# RT1052_MB.net
KiCad netlist of a schematic drawn in Altium Designer
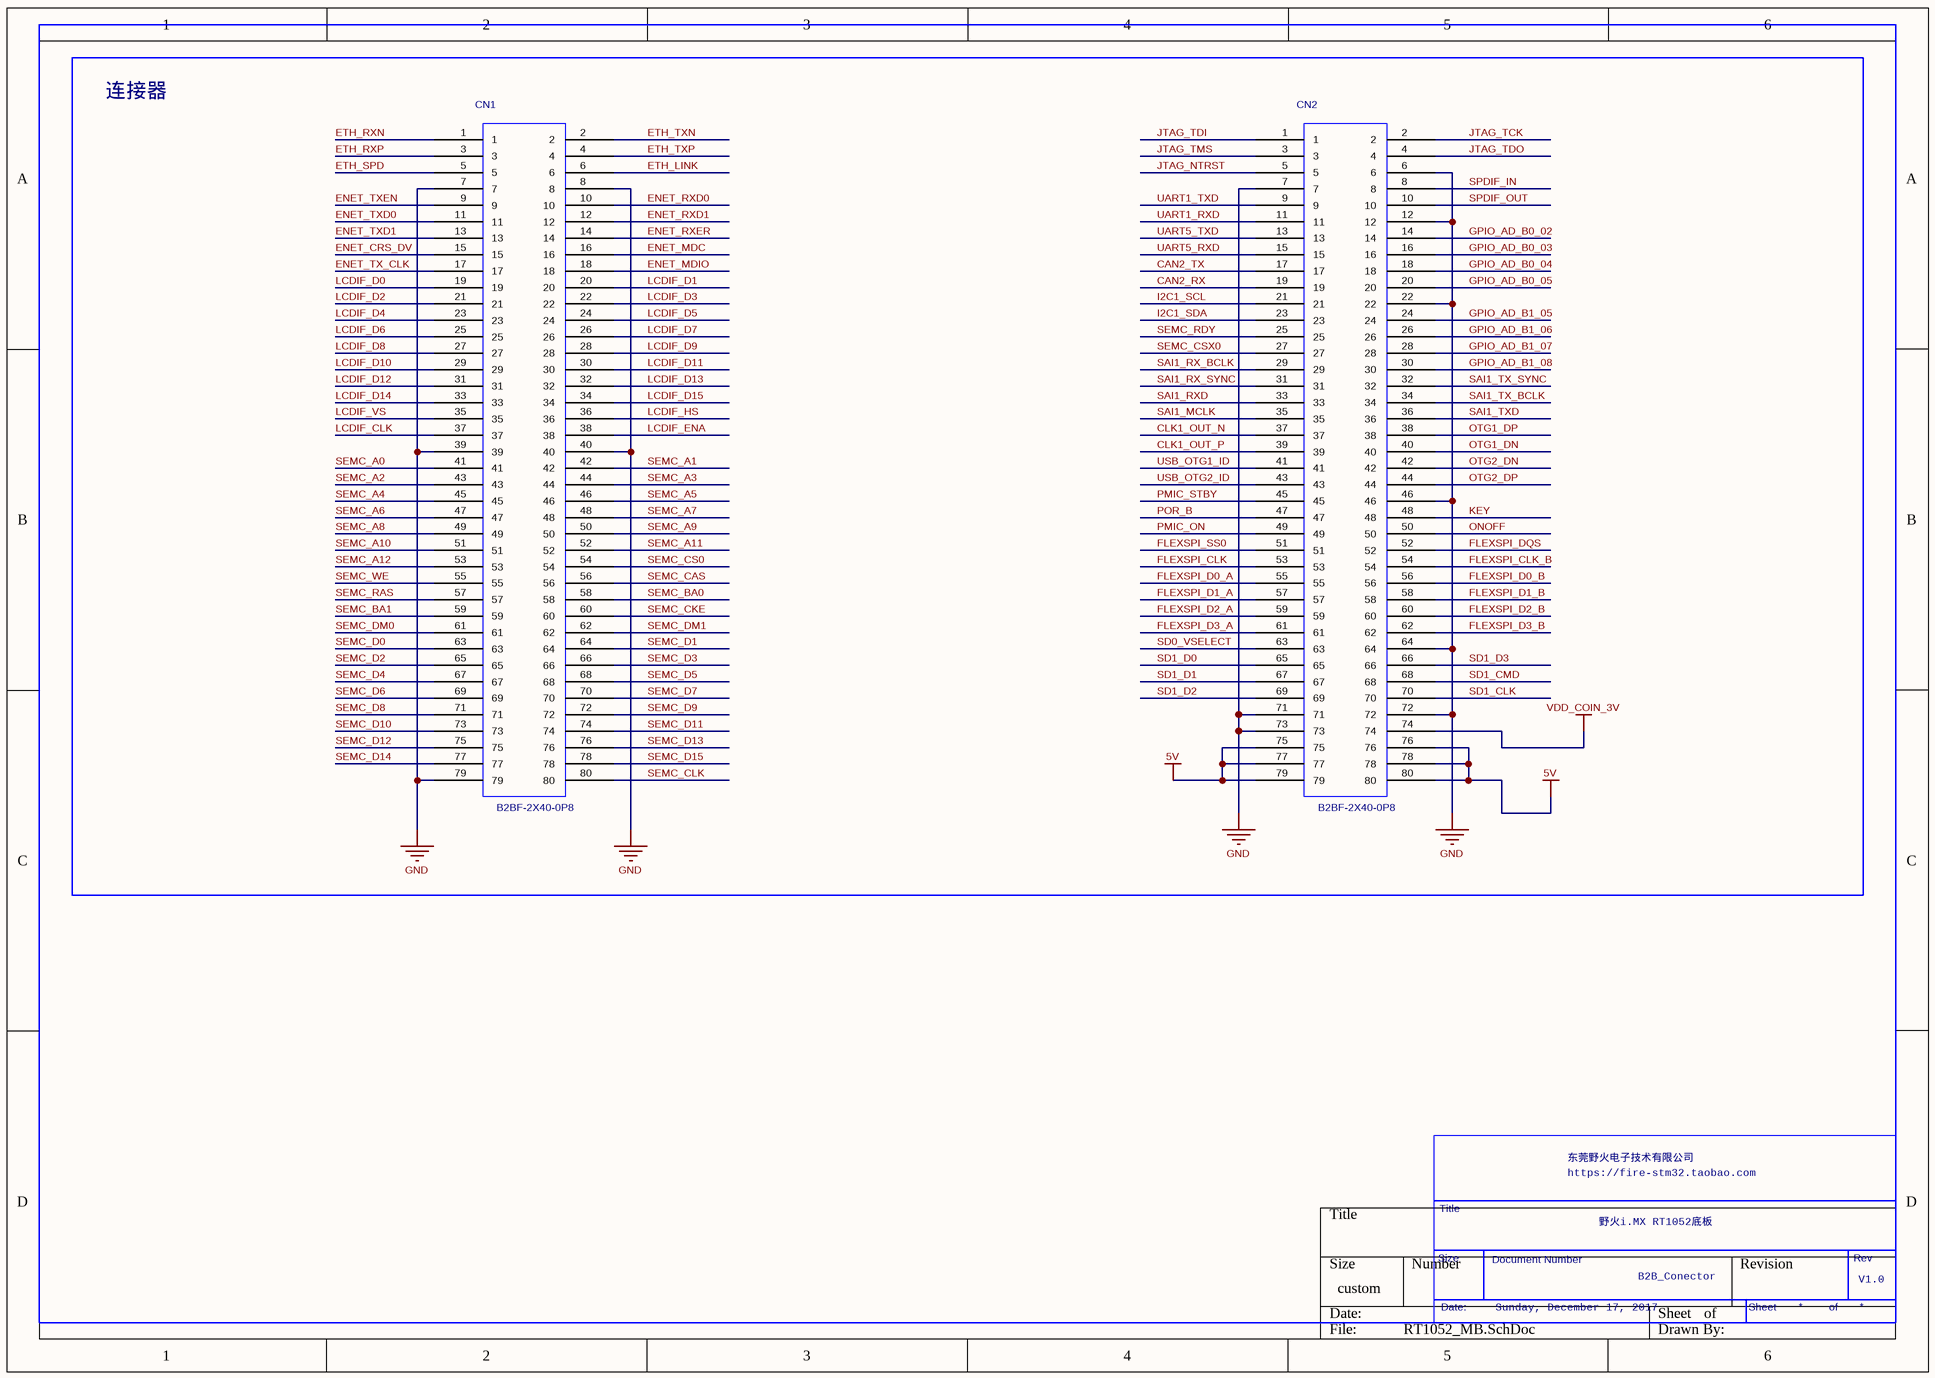
[diagram p0: RT1052_MB.SchDoc]

(export (version "E")
  (design (tool "Eeschema 10.0.6"))
  (components
    (comp (ref "CN1")
      (value "B2BF-2X40-0P8")
      (footprint "B2BF-2X40-0P8")
      (fields (field (name "Comment") "B2B_2X40_0_8MM"))
      (libsource (lib "*") (part "B2B_2X40_0_8MM"))
    )
    (comp (ref "CN2")
      (value "B2BF-2X40-0P8")
      (footprint "B2BF-2X40-0P8")
      (fields (field (name "Comment") "B2B_2X40_0_8MM"))
      (libsource (lib "*") (part "B2B_2X40_0_8MM"))
    )
  )
  (nets
    (net (code "1") (name "/CAN2_RX") (class "Default")
      (node (ref "CN2") (pin "19") (pinfunction "19_19") (pintype "passive"))
    )
    (net (code "2") (name "/CAN2_TX") (class "Default")
      (node (ref "CN2") (pin "17") (pinfunction "17_17") (pintype "passive"))
    )
    (net (code "3") (name "/CLK1_OUT_N") (class "Default")
      (node (ref "CN2") (pin "37") (pinfunction "37_37") (pintype "passive"))
    )
    (net (code "4") (name "/CLK1_OUT_P") (class "Default")
      (node (ref "CN2") (pin "39") (pinfunction "39_39") (pintype "passive"))
    )
    (net (code "5") (name "/ENET_CRS_DV") (class "Default")
      (node (ref "CN1") (pin "15") (pinfunction "15_15") (pintype "passive"))
    )
    (net (code "6") (name "/ENET_MDC") (class "Default")
      (node (ref "CN1") (pin "16") (pinfunction "16_16") (pintype "passive"))
    )
    (net (code "7") (name "/ENET_MDIO") (class "Default")
      (node (ref "CN1") (pin "18") (pinfunction "18_18") (pintype "passive"))
    )
    (net (code "8") (name "/ENET_RXD0") (class "Default")
      (node (ref "CN1") (pin "10") (pinfunction "10_10") (pintype "passive"))
    )
    (net (code "9") (name "/ENET_RXD1") (class "Default")
      (node (ref "CN1") (pin "12") (pinfunction "12_12") (pintype "passive"))
    )
    (net (code "10") (name "/ENET_RXER") (class "Default")
      (node (ref "CN1") (pin "14") (pinfunction "14_14") (pintype "passive"))
    )
    (net (code "11") (name "/ENET_TXD0") (class "Default")
      (node (ref "CN1") (pin "11") (pinfunction "11_11") (pintype "passive"))
    )
    (net (code "12") (name "/ENET_TXD1") (class "Default")
      (node (ref "CN1") (pin "13") (pinfunction "13_13") (pintype "passive"))
    )
    (net (code "13") (name "/ENET_TXEN") (class "Default")
      (node (ref "CN1") (pin "9") (pinfunction "9_9") (pintype "passive"))
    )
    (net (code "14") (name "/ENET_TX_CLK") (class "Default")
      (node (ref "CN1") (pin "17") (pinfunction "17_17") (pintype "passive"))
    )
    (net (code "15") (name "/ETH_LINK") (class "Default")
      (node (ref "CN1") (pin "6") (pinfunction "6_6") (pintype "passive"))
    )
    (net (code "16") (name "/ETH_RXN") (class "Default")
      (node (ref "CN1") (pin "1") (pinfunction "1_1") (pintype "passive"))
    )
    (net (code "17") (name "/ETH_RXP") (class "Default")
      (node (ref "CN1") (pin "3") (pinfunction "3_3") (pintype "passive"))
    )
    (net (code "18") (name "/ETH_SPD") (class "Default")
      (node (ref "CN1") (pin "5") (pinfunction "5_5") (pintype "passive"))
    )
    (net (code "19") (name "/ETH_TXN") (class "Default")
      (node (ref "CN1") (pin "2") (pinfunction "2_2") (pintype "passive"))
    )
    (net (code "20") (name "/ETH_TXP") (class "Default")
      (node (ref "CN1") (pin "4") (pinfunction "4_4") (pintype "passive"))
    )
    (net (code "21") (name "/FLEXSPI_CLK") (class "Default")
      (node (ref "CN2") (pin "53") (pinfunction "53_53") (pintype "passive"))
    )
    (net (code "22") (name "/FLEXSPI_CLK_B") (class "Default")
      (node (ref "CN2") (pin "54") (pinfunction "54_54") (pintype "passive"))
    )
    (net (code "23") (name "/FLEXSPI_D0_A") (class "Default")
      (node (ref "CN2") (pin "55") (pinfunction "55_55") (pintype "passive"))
    )
    (net (code "24") (name "/FLEXSPI_D0_B") (class "Default")
      (node (ref "CN2") (pin "56") (pinfunction "56_56") (pintype "passive"))
    )
    (net (code "25") (name "/FLEXSPI_D1_A") (class "Default")
      (node (ref "CN2") (pin "57") (pinfunction "57_57") (pintype "passive"))
    )
    (net (code "26") (name "/FLEXSPI_D1_B") (class "Default")
      (node (ref "CN2") (pin "58") (pinfunction "58_58") (pintype "passive"))
    )
    (net (code "27") (name "/FLEXSPI_D2_A") (class "Default")
      (node (ref "CN2") (pin "59") (pinfunction "59_59") (pintype "passive"))
    )
    (net (code "28") (name "/FLEXSPI_D2_B") (class "Default")
      (node (ref "CN2") (pin "60") (pinfunction "60_60") (pintype "passive"))
    )
    (net (code "29") (name "/FLEXSPI_D3_A") (class "Default")
      (node (ref "CN2") (pin "61") (pinfunction "61_61") (pintype "passive"))
    )
    (net (code "30") (name "/FLEXSPI_D3_B") (class "Default")
      (node (ref "CN2") (pin "62") (pinfunction "62_62") (pintype "passive"))
    )
    (net (code "31") (name "/FLEXSPI_DQS") (class "Default")
      (node (ref "CN2") (pin "52") (pinfunction "52_52") (pintype "passive"))
    )
    (net (code "32") (name "/FLEXSPI_SS0") (class "Default")
      (node (ref "CN2") (pin "51") (pinfunction "51_51") (pintype "passive"))
    )
    (net (code "33") (name "/GPIO_AD_B0_02") (class "Default")
      (node (ref "CN2") (pin "14") (pinfunction "14_14") (pintype "passive"))
    )
    (net (code "34") (name "/GPIO_AD_B0_03") (class "Default")
      (node (ref "CN2") (pin "16") (pinfunction "16_16") (pintype "passive"))
    )
    (net (code "35") (name "/GPIO_AD_B0_04") (class "Default")
      (node (ref "CN2") (pin "18") (pinfunction "18_18") (pintype "passive"))
    )
    (net (code "36") (name "/GPIO_AD_B0_05") (class "Default")
      (node (ref "CN2") (pin "20") (pinfunction "20_20") (pintype "passive"))
    )
    (net (code "37") (name "/GPIO_AD_B1_05") (class "Default")
      (node (ref "CN2") (pin "24") (pinfunction "24_24") (pintype "passive"))
    )
    (net (code "38") (name "/GPIO_AD_B1_06") (class "Default")
      (node (ref "CN2") (pin "26") (pinfunction "26_26") (pintype "passive"))
    )
    (net (code "39") (name "/GPIO_AD_B1_07") (class "Default")
      (node (ref "CN2") (pin "28") (pinfunction "28_28") (pintype "passive"))
    )
    (net (code "40") (name "/GPIO_AD_B1_08") (class "Default")
      (node (ref "CN2") (pin "30") (pinfunction "30_30") (pintype "passive"))
    )
    (net (code "41") (name "/I2C1_SCL") (class "Default")
      (node (ref "CN2") (pin "21") (pinfunction "21_21") (pintype "passive"))
    )
    (net (code "42") (name "/I2C1_SDA") (class "Default")
      (node (ref "CN2") (pin "23") (pinfunction "23_23") (pintype "passive"))
    )
    (net (code "43") (name "/JTAG_NTRST") (class "Default")
      (node (ref "CN2") (pin "5") (pinfunction "5_5") (pintype "passive"))
    )
    (net (code "44") (name "/JTAG_TCK") (class "Default")
      (node (ref "CN2") (pin "2") (pinfunction "2_2") (pintype "passive"))
    )
    (net (code "45") (name "/JTAG_TDI") (class "Default")
      (node (ref "CN2") (pin "1") (pinfunction "1_1") (pintype "passive"))
    )
    (net (code "46") (name "/JTAG_TDO") (class "Default")
      (node (ref "CN2") (pin "4") (pinfunction "4_4") (pintype "passive"))
    )
    (net (code "47") (name "/JTAG_TMS") (class "Default")
      (node (ref "CN2") (pin "3") (pinfunction "3_3") (pintype "passive"))
    )
    (net (code "48") (name "/KEY") (class "Default")
      (node (ref "CN2") (pin "48") (pinfunction "48_48") (pintype "passive"))
    )
    (net (code "49") (name "/LCDIF_CLK") (class "Default")
      (node (ref "CN1") (pin "37") (pinfunction "37_37") (pintype "passive"))
    )
    (net (code "50") (name "/LCDIF_D0") (class "Default")
      (node (ref "CN1") (pin "19") (pinfunction "19_19") (pintype "passive"))
    )
    (net (code "51") (name "/LCDIF_D1") (class "Default")
      (node (ref "CN1") (pin "20") (pinfunction "20_20") (pintype "passive"))
    )
    (net (code "52") (name "/LCDIF_D2") (class "Default")
      (node (ref "CN1") (pin "21") (pinfunction "21_21") (pintype "passive"))
    )
    (net (code "53") (name "/LCDIF_D3") (class "Default")
      (node (ref "CN1") (pin "22") (pinfunction "22_22") (pintype "passive"))
    )
    (net (code "54") (name "/LCDIF_D4") (class "Default")
      (node (ref "CN1") (pin "23") (pinfunction "23_23") (pintype "passive"))
    )
    (net (code "55") (name "/LCDIF_D5") (class "Default")
      (node (ref "CN1") (pin "24") (pinfunction "24_24") (pintype "passive"))
    )
    (net (code "56") (name "/LCDIF_D6") (class "Default")
      (node (ref "CN1") (pin "25") (pinfunction "25_25") (pintype "passive"))
    )
    (net (code "57") (name "/LCDIF_D7") (class "Default")
      (node (ref "CN1") (pin "26") (pinfunction "26_26") (pintype "passive"))
    )
    (net (code "58") (name "/LCDIF_D8") (class "Default")
      (node (ref "CN1") (pin "27") (pinfunction "27_27") (pintype "passive"))
    )
    (net (code "59") (name "/LCDIF_D9") (class "Default")
      (node (ref "CN1") (pin "28") (pinfunction "28_28") (pintype "passive"))
    )
    (net (code "60") (name "/LCDIF_D10") (class "Default")
      (node (ref "CN1") (pin "29") (pinfunction "29_29") (pintype "passive"))
    )
    (net (code "61") (name "/LCDIF_D11") (class "Default")
      (node (ref "CN1") (pin "30") (pinfunction "30_30") (pintype "passive"))
    )
    (net (code "62") (name "/LCDIF_D12") (class "Default")
      (node (ref "CN1") (pin "31") (pinfunction "31_31") (pintype "passive"))
    )
    (net (code "63") (name "/LCDIF_D13") (class "Default")
      (node (ref "CN1") (pin "32") (pinfunction "32_32") (pintype "passive"))
    )
    (net (code "64") (name "/LCDIF_D14") (class "Default")
      (node (ref "CN1") (pin "33") (pinfunction "33_33") (pintype "passive"))
    )
    (net (code "65") (name "/LCDIF_D15") (class "Default")
      (node (ref "CN1") (pin "34") (pinfunction "34_34") (pintype "passive"))
    )
    (net (code "66") (name "/LCDIF_ENA") (class "Default")
      (node (ref "CN1") (pin "38") (pinfunction "38_38") (pintype "passive"))
    )
    (net (code "67") (name "/LCDIF_HS") (class "Default")
      (node (ref "CN1") (pin "36") (pinfunction "36_36") (pintype "passive"))
    )
    (net (code "68") (name "/LCDIF_VS") (class "Default")
      (node (ref "CN1") (pin "35") (pinfunction "35_35") (pintype "passive"))
    )
    (net (code "69") (name "/ONOFF") (class "Default")
      (node (ref "CN2") (pin "50") (pinfunction "50_50") (pintype "passive"))
    )
    (net (code "70") (name "/OTG1_DN") (class "Default")
      (node (ref "CN2") (pin "40") (pinfunction "40_40") (pintype "passive"))
    )
    (net (code "71") (name "/OTG1_DP") (class "Default")
      (node (ref "CN2") (pin "38") (pinfunction "38_38") (pintype "passive"))
    )
    (net (code "72") (name "/OTG2_DN") (class "Default")
      (node (ref "CN2") (pin "42") (pinfunction "42_42") (pintype "passive"))
    )
    (net (code "73") (name "/OTG2_DP") (class "Default")
      (node (ref "CN2") (pin "44") (pinfunction "44_44") (pintype "passive"))
    )
    (net (code "74") (name "/PMIC_ON") (class "Default")
      (node (ref "CN2") (pin "49") (pinfunction "49_49") (pintype "passive"))
    )
    (net (code "75") (name "/PMIC_STBY") (class "Default")
      (node (ref "CN2") (pin "45") (pinfunction "45_45") (pintype "passive"))
    )
    (net (code "76") (name "/POR_B") (class "Default")
      (node (ref "CN2") (pin "47") (pinfunction "47_47") (pintype "passive"))
    )
    (net (code "77") (name "/SAI1_MCLK") (class "Default")
      (node (ref "CN2") (pin "35") (pinfunction "35_35") (pintype "passive"))
    )
    (net (code "78") (name "/SAI1_RXD") (class "Default")
      (node (ref "CN2") (pin "33") (pinfunction "33_33") (pintype "passive"))
    )
    (net (code "79") (name "/SAI1_RX_BCLK") (class "Default")
      (node (ref "CN2") (pin "29") (pinfunction "29_29") (pintype "passive"))
    )
    (net (code "80") (name "/SAI1_RX_SYNC") (class "Default")
      (node (ref "CN2") (pin "31") (pinfunction "31_31") (pintype "passive"))
    )
    (net (code "81") (name "/SAI1_TXD") (class "Default")
      (node (ref "CN2") (pin "36") (pinfunction "36_36") (pintype "passive"))
    )
    (net (code "82") (name "/SAI1_TX_BCLK") (class "Default")
      (node (ref "CN2") (pin "34") (pinfunction "34_34") (pintype "passive"))
    )
    (net (code "83") (name "/SAI1_TX_SYNC") (class "Default")
      (node (ref "CN2") (pin "32") (pinfunction "32_32") (pintype "passive"))
    )
    (net (code "84") (name "/SD0_VSELECT") (class "Default")
      (node (ref "CN2") (pin "63") (pinfunction "63_63") (pintype "passive"))
    )
    (net (code "85") (name "/SD1_CLK") (class "Default")
      (node (ref "CN2") (pin "70") (pinfunction "70_70") (pintype "passive"))
    )
    (net (code "86") (name "/SD1_CMD") (class "Default")
      (node (ref "CN2") (pin "68") (pinfunction "68_68") (pintype "passive"))
    )
    (net (code "87") (name "/SD1_D0") (class "Default")
      (node (ref "CN2") (pin "65") (pinfunction "65_65") (pintype "passive"))
    )
    (net (code "88") (name "/SD1_D1") (class "Default")
      (node (ref "CN2") (pin "67") (pinfunction "67_67") (pintype "passive"))
    )
    (net (code "89") (name "/SD1_D2") (class "Default")
      (node (ref "CN2") (pin "69") (pinfunction "69_69") (pintype "passive"))
    )
    (net (code "90") (name "/SD1_D3") (class "Default")
      (node (ref "CN2") (pin "66") (pinfunction "66_66") (pintype "passive"))
    )
    (net (code "91") (name "/SEMC_A0") (class "Default")
      (node (ref "CN1") (pin "41") (pinfunction "41_41") (pintype "passive"))
    )
    (net (code "92") (name "/SEMC_A1") (class "Default")
      (node (ref "CN1") (pin "42") (pinfunction "42_42") (pintype "passive"))
    )
    (net (code "93") (name "/SEMC_A2") (class "Default")
      (node (ref "CN1") (pin "43") (pinfunction "43_43") (pintype "passive"))
    )
    (net (code "94") (name "/SEMC_A3") (class "Default")
      (node (ref "CN1") (pin "44") (pinfunction "44_44") (pintype "passive"))
    )
    (net (code "95") (name "/SEMC_A4") (class "Default")
      (node (ref "CN1") (pin "45") (pinfunction "45_45") (pintype "passive"))
    )
    (net (code "96") (name "/SEMC_A5") (class "Default")
      (node (ref "CN1") (pin "46") (pinfunction "46_46") (pintype "passive"))
    )
    (net (code "97") (name "/SEMC_A6") (class "Default")
      (node (ref "CN1") (pin "47") (pinfunction "47_47") (pintype "passive"))
    )
    (net (code "98") (name "/SEMC_A7") (class "Default")
      (node (ref "CN1") (pin "48") (pinfunction "48_48") (pintype "passive"))
    )
    (net (code "99") (name "/SEMC_A8") (class "Default")
      (node (ref "CN1") (pin "49") (pinfunction "49_49") (pintype "passive"))
    )
    (net (code "100") (name "/SEMC_A9") (class "Default")
      (node (ref "CN1") (pin "50") (pinfunction "50_50") (pintype "passive"))
    )
    (net (code "101") (name "/SEMC_A10") (class "Default")
      (node (ref "CN1") (pin "51") (pinfunction "51_51") (pintype "passive"))
    )
    (net (code "102") (name "/SEMC_A11") (class "Default")
      (node (ref "CN1") (pin "52") (pinfunction "52_52") (pintype "passive"))
    )
    (net (code "103") (name "/SEMC_A12") (class "Default")
      (node (ref "CN1") (pin "53") (pinfunction "53_53") (pintype "passive"))
    )
    (net (code "104") (name "/SEMC_BA0") (class "Default")
      (node (ref "CN1") (pin "58") (pinfunction "58_58") (pintype "passive"))
    )
    (net (code "105") (name "/SEMC_BA1") (class "Default")
      (node (ref "CN1") (pin "59") (pinfunction "59_59") (pintype "passive"))
    )
    (net (code "106") (name "/SEMC_CAS") (class "Default")
      (node (ref "CN1") (pin "56") (pinfunction "56_56") (pintype "passive"))
    )
    (net (code "107") (name "/SEMC_CKE") (class "Default")
      (node (ref "CN1") (pin "60") (pinfunction "60_60") (pintype "passive"))
    )
    (net (code "108") (name "/SEMC_CLK") (class "Default")
      (node (ref "CN1") (pin "80") (pinfunction "80_80") (pintype "passive"))
    )
    (net (code "109") (name "/SEMC_CS0") (class "Default")
      (node (ref "CN1") (pin "54") (pinfunction "54_54") (pintype "passive"))
    )
    (net (code "110") (name "/SEMC_CSX0") (class "Default")
      (node (ref "CN2") (pin "27") (pinfunction "27_27") (pintype "passive"))
    )
    (net (code "111") (name "/SEMC_D0") (class "Default")
      (node (ref "CN1") (pin "63") (pinfunction "63_63") (pintype "passive"))
    )
    (net (code "112") (name "/SEMC_D1") (class "Default")
      (node (ref "CN1") (pin "64") (pinfunction "64_64") (pintype "passive"))
    )
    (net (code "113") (name "/SEMC_D2") (class "Default")
      (node (ref "CN1") (pin "65") (pinfunction "65_65") (pintype "passive"))
    )
    (net (code "114") (name "/SEMC_D3") (class "Default")
      (node (ref "CN1") (pin "66") (pinfunction "66_66") (pintype "passive"))
    )
    (net (code "115") (name "/SEMC_D4") (class "Default")
      (node (ref "CN1") (pin "67") (pinfunction "67_67") (pintype "passive"))
    )
    (net (code "116") (name "/SEMC_D5") (class "Default")
      (node (ref "CN1") (pin "68") (pinfunction "68_68") (pintype "passive"))
    )
    (net (code "117") (name "/SEMC_D6") (class "Default")
      (node (ref "CN1") (pin "69") (pinfunction "69_69") (pintype "passive"))
    )
    (net (code "118") (name "/SEMC_D7") (class "Default")
      (node (ref "CN1") (pin "70") (pinfunction "70_70") (pintype "passive"))
    )
    (net (code "119") (name "/SEMC_D8") (class "Default")
      (node (ref "CN1") (pin "71") (pinfunction "71_71") (pintype "passive"))
    )
    (net (code "120") (name "/SEMC_D9") (class "Default")
      (node (ref "CN1") (pin "72") (pinfunction "72_72") (pintype "passive"))
    )
    (net (code "121") (name "/SEMC_D10") (class "Default")
      (node (ref "CN1") (pin "73") (pinfunction "73_73") (pintype "passive"))
    )
    (net (code "122") (name "/SEMC_D11") (class "Default")
      (node (ref "CN1") (pin "74") (pinfunction "74_74") (pintype "passive"))
    )
    (net (code "123") (name "/SEMC_D12") (class "Default")
      (node (ref "CN1") (pin "75") (pinfunction "75_75") (pintype "passive"))
    )
    (net (code "124") (name "/SEMC_D13") (class "Default")
      (node (ref "CN1") (pin "76") (pinfunction "76_76") (pintype "passive"))
    )
    (net (code "125") (name "/SEMC_D14") (class "Default")
      (node (ref "CN1") (pin "77") (pinfunction "77_77") (pintype "passive"))
    )
    (net (code "126") (name "/SEMC_D15") (class "Default")
      (node (ref "CN1") (pin "78") (pinfunction "78_78") (pintype "passive"))
    )
    (net (code "127") (name "/SEMC_DM0") (class "Default")
      (node (ref "CN1") (pin "61") (pinfunction "61_61") (pintype "passive"))
    )
    (net (code "128") (name "/SEMC_DM1") (class "Default")
      (node (ref "CN1") (pin "62") (pinfunction "62_62") (pintype "passive"))
    )
    (net (code "129") (name "/SEMC_RAS") (class "Default")
      (node (ref "CN1") (pin "57") (pinfunction "57_57") (pintype "passive"))
    )
    (net (code "130") (name "/SEMC_RDY") (class "Default")
      (node (ref "CN2") (pin "25") (pinfunction "25_25") (pintype "passive"))
    )
    (net (code "131") (name "/SEMC_WE") (class "Default")
      (node (ref "CN1") (pin "55") (pinfunction "55_55") (pintype "passive"))
    )
    (net (code "132") (name "/SPDIF_IN") (class "Default")
      (node (ref "CN2") (pin "8") (pinfunction "8_8") (pintype "passive"))
    )
    (net (code "133") (name "/SPDIF_OUT") (class "Default")
      (node (ref "CN2") (pin "10") (pinfunction "10_10") (pintype "passive"))
    )
    (net (code "134") (name "/UART1_RXD") (class "Default")
      (node (ref "CN2") (pin "11") (pinfunction "11_11") (pintype "passive"))
    )
    (net (code "135") (name "/UART1_TXD") (class "Default")
      (node (ref "CN2") (pin "9") (pinfunction "9_9") (pintype "passive"))
    )
    (net (code "136") (name "/UART5_RXD") (class "Default")
      (node (ref "CN2") (pin "15") (pinfunction "15_15") (pintype "passive"))
    )
    (net (code "137") (name "/UART5_TXD") (class "Default")
      (node (ref "CN2") (pin "13") (pinfunction "13_13") (pintype "passive"))
    )
    (net (code "138") (name "/USB_OTG1_ID") (class "Default")
      (node (ref "CN2") (pin "41") (pinfunction "41_41") (pintype "passive"))
    )
    (net (code "139") (name "/USB_OTG2_ID") (class "Default")
      (node (ref "CN2") (pin "43") (pinfunction "43_43") (pintype "passive"))
    )
    (net (code "140") (name "5V") (class "Default")
      (node (ref "CN2") (pin "75") (pinfunction "75_75") (pintype "passive"))
      (node (ref "CN2") (pin "76") (pinfunction "76_76") (pintype "passive"))
      (node (ref "CN2") (pin "77") (pinfunction "77_77") (pintype "passive"))
      (node (ref "CN2") (pin "78") (pinfunction "78_78") (pintype "passive"))
      (node (ref "CN2") (pin "79") (pinfunction "79_79") (pintype "passive"))
      (node (ref "CN2") (pin "80") (pinfunction "80_80") (pintype "passive"))
    )
    (net (code "141") (name "GND") (class "Default")
      (node (ref "CN1") (pin "39") (pinfunction "39_39") (pintype "passive"))
      (node (ref "CN1") (pin "40") (pinfunction "40_40") (pintype "passive"))
      (node (ref "CN1") (pin "7") (pinfunction "7_7") (pintype "passive"))
      (node (ref "CN1") (pin "79") (pinfunction "79_79") (pintype "passive"))
      (node (ref "CN1") (pin "8") (pinfunction "8_8") (pintype "passive"))
      (node (ref "CN2") (pin "12") (pinfunction "12_12") (pintype "passive"))
      (node (ref "CN2") (pin "22") (pinfunction "22_22") (pintype "passive"))
      (node (ref "CN2") (pin "46") (pinfunction "46_46") (pintype "passive"))
      (node (ref "CN2") (pin "6") (pinfunction "6_6") (pintype "passive"))
      (node (ref "CN2") (pin "64") (pinfunction "64_64") (pintype "passive"))
      (node (ref "CN2") (pin "7") (pinfunction "7_7") (pintype "passive"))
      (node (ref "CN2") (pin "71") (pinfunction "71_71") (pintype "passive"))
      (node (ref "CN2") (pin "72") (pinfunction "72_72") (pintype "passive"))
      (node (ref "CN2") (pin "73") (pinfunction "73_73") (pintype "passive"))
    )
    (net (code "142") (name "VDD_COIN_3V") (class "Default")
      (node (ref "CN2") (pin "74") (pinfunction "74_74") (pintype "passive"))
    )
  )
)
